# ver1_0.net
KiCad netlist of a schematic drawn in EAGLE
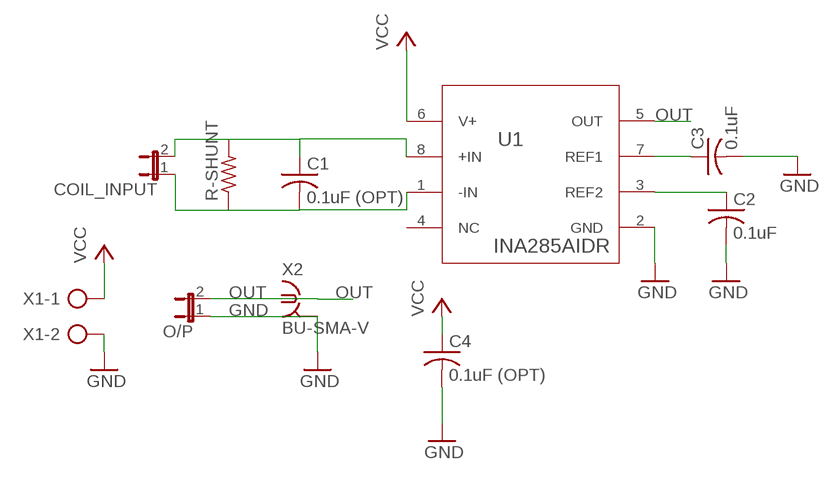
[diagram p0: schematic, sheet 1]

(export (version "E")
  (design (tool "Eeschema 10.0.6"))
  (components
    (comp (ref "C1")
      (value "0.1uF (OPT)")
      (footprint "eagle-import:C0603")
      (libsource (lib "eagle-import") (part "C-USC0603"))
    )
    (comp (ref "C2")
      (value "0.1uF")
      (footprint "eagle-import:C0603")
      (libsource (lib "eagle-import") (part "C-USC0603"))
    )
    (comp (ref "C3")
      (value "0.1uF")
      (footprint "eagle-import:C0603")
      (libsource (lib "eagle-import") (part "C-USC0603"))
    )
    (comp (ref "C4")
      (value "0.1uF (OPT)")
      (footprint "eagle-import:C0603")
      (libsource (lib "eagle-import") (part "C-USC0603"))
    )
    (comp (ref "COIL_INPUT")
      (value "JP1E")
      (footprint "eagle-import:JP1")
      (libsource (lib "eagle-import") (part "JP1E"))
    )
    (comp (ref "O/P")
      (value "JP1E")
      (footprint "eagle-import:JP1")
      (libsource (lib "eagle-import") (part "JP1E"))
    )
    (comp (ref "R-SHUNT")
      (value "R-US_R0603")
      (footprint "eagle-import:R0603")
      (libsource (lib "eagle-import") (part "R-US_R0603"))
    )
    (comp (ref "U1")
      (value "INA285AIDR")
      (footprint "eagle-import:D0008A_M")
      (libsource (lib "eagle-import") (part "INA285AIDR"))
    )
    (comp (ref "X1")
      (value "AK500/2")
      (footprint "eagle-import:AK500_2")
      (libsource (lib "eagle-import") (part "AK500/2"))
    )
    (comp (ref "X2")
      (value "BU-SMA-V")
      (footprint "eagle-import:BU-SMA-V")
      (libsource (lib "eagle-import") (part "BU-SMA-V"))
    )
  )
  (nets
    (net (code "1") (name "/OUT") (class "Default")
      (node (ref "O/P") (pin "2") (pinfunction "2_2") (pintype "passive"))
      (node (ref "U1") (pin "5") (pinfunction "OUT_5") (pintype "output"))
      (node (ref "X2") (pin "1") (pinfunction "1_1") (pintype "passive"))
    )
    (net (code "2") (name "GND") (class "Default")
      (node (ref "C2") (pin "2") (pinfunction "2_2") (pintype "passive"))
      (node (ref "C3") (pin "2") (pinfunction "2_2") (pintype "passive"))
      (node (ref "C4") (pin "2") (pinfunction "2_2") (pintype "passive"))
      (node (ref "O/P") (pin "1") (pinfunction "1_1") (pintype "passive"))
      (node (ref "U1") (pin "2") (pinfunction "GND_2") (pintype "power_in"))
      (node (ref "X1") (pin "2") (pinfunction "KL_2") (pintype "passive"))
      (node (ref "X2") (pin "2") (pinfunction "2_2") (pintype "passive"))
      (node (ref "X2") (pin "3") (pinfunction "2_3") (pintype "passive"))
      (node (ref "X2") (pin "4") (pinfunction "2_4") (pintype "passive"))
      (node (ref "X2") (pin "5") (pinfunction "2_5") (pintype "passive"))
    )
    (net (code "3") (name "Net-(U1-+IN)") (class "Default")
      (node (ref "C1") (pin "1") (pinfunction "1_1") (pintype "passive"))
      (node (ref "COIL_INPUT") (pin "2") (pinfunction "2_2") (pintype "passive"))
      (node (ref "R-SHUNT") (pin "2") (pinfunction "2_2") (pintype "passive"))
      (node (ref "U1") (pin "8") (pinfunction "+IN_8") (pintype "input"))
    )
    (net (code "4") (name "Net-(U1--IN)") (class "Default")
      (node (ref "C1") (pin "2") (pinfunction "2_2") (pintype "passive"))
      (node (ref "COIL_INPUT") (pin "1") (pinfunction "1_1") (pintype "passive"))
      (node (ref "R-SHUNT") (pin "1") (pinfunction "1_1") (pintype "passive"))
      (node (ref "U1") (pin "1") (pinfunction "-IN_1") (pintype "input"))
    )
    (net (code "5") (name "Net-(U1-REF1)") (class "Default")
      (node (ref "C3") (pin "1") (pinfunction "1_1") (pintype "passive"))
      (node (ref "U1") (pin "7") (pinfunction "REF1_7") (pintype "input"))
    )
    (net (code "6") (name "Net-(U1-REF2)") (class "Default")
      (node (ref "C2") (pin "1") (pinfunction "1_1") (pintype "passive"))
      (node (ref "U1") (pin "3") (pinfunction "REF2_3") (pintype "input"))
    )
    (net (code "7") (name "VCC") (class "Default")
      (node (ref "C4") (pin "1") (pinfunction "1_1") (pintype "passive"))
      (node (ref "U1") (pin "6") (pinfunction "V+_6") (pintype "power_in"))
      (node (ref "X1") (pin "1") (pinfunction "KL_1") (pintype "passive"))
    )
    (net (code "8") (name "unconnected-(U1-NC-Pad4)") (class "Default")
      (node (ref "U1") (pin "4") (pinfunction "NC_4") (pintype "passive"))
    )
  )
)
